# Top.net
KiCad netlist of a schematic drawn in Altium Designer
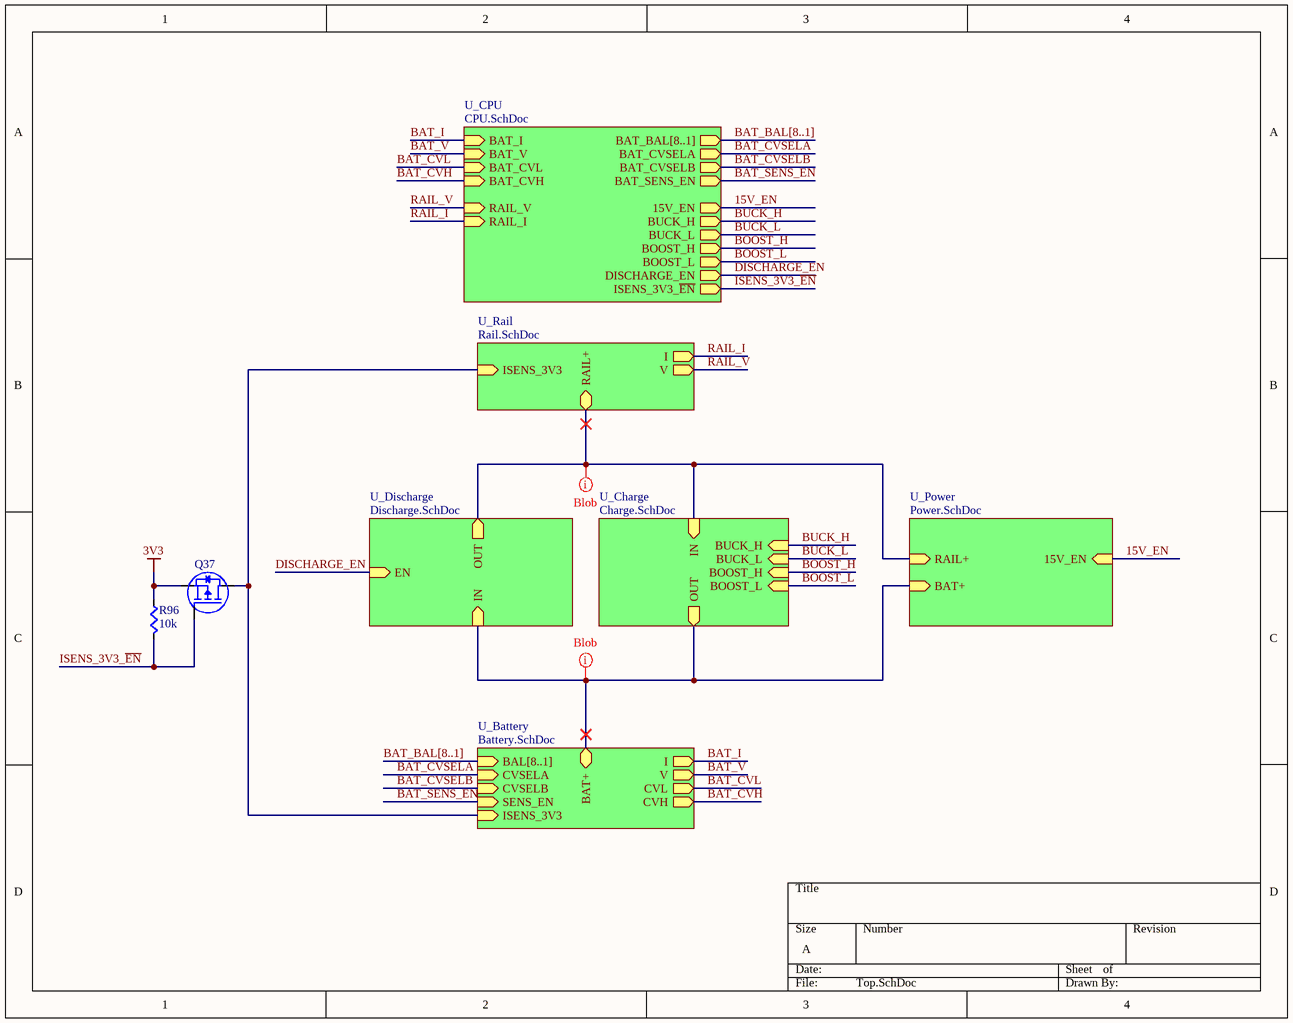
[diagram p0: Top.SchDoc]

(export (version "E")
  (design (tool "Eeschema 10.0.6"))
  (components
    (comp (ref "Q37")
      (value "FDN5618P")
      (footprint "PowerSOT-3")
      (description "60V P-Channel Logic Level PowerTrench MOSFET")
      (libsource (lib "SubjuGator8") (part "FDN5618P"))
    )
    (comp (ref "R96")
      (value "10k")
      (footprint "RES0603")
      (fields (field (name "Comment") "Res"))
      (libsource (lib "SubjuGator8") (part "Res"))
    )
  )
  (nets
    (net (code "23") (name "/ISENS_3V3") (class "Default")
      (node (ref "Q37") (pin "D") (pinfunction "D_D") (pintype "passive"))
    )
    (net (code "24") (name "/ISENS_3V3_~{EN}") (class "Default")
      (node (ref "Q37") (pin "G") (pinfunction "G_G") (pintype "passive"))
      (node (ref "R96") (pin "2") (pinfunction "B_2") (pintype "passive"))
    )
    (net (code "29") (name "3V3") (class "Default")
      (node (ref "Q37") (pin "S") (pinfunction "S_S") (pintype "passive"))
      (node (ref "R96") (pin "1") (pinfunction "A_1") (pintype "passive"))
    )
  )
)
